# Sheet3.net
KiCad netlist of a schematic drawn in Altium Designer
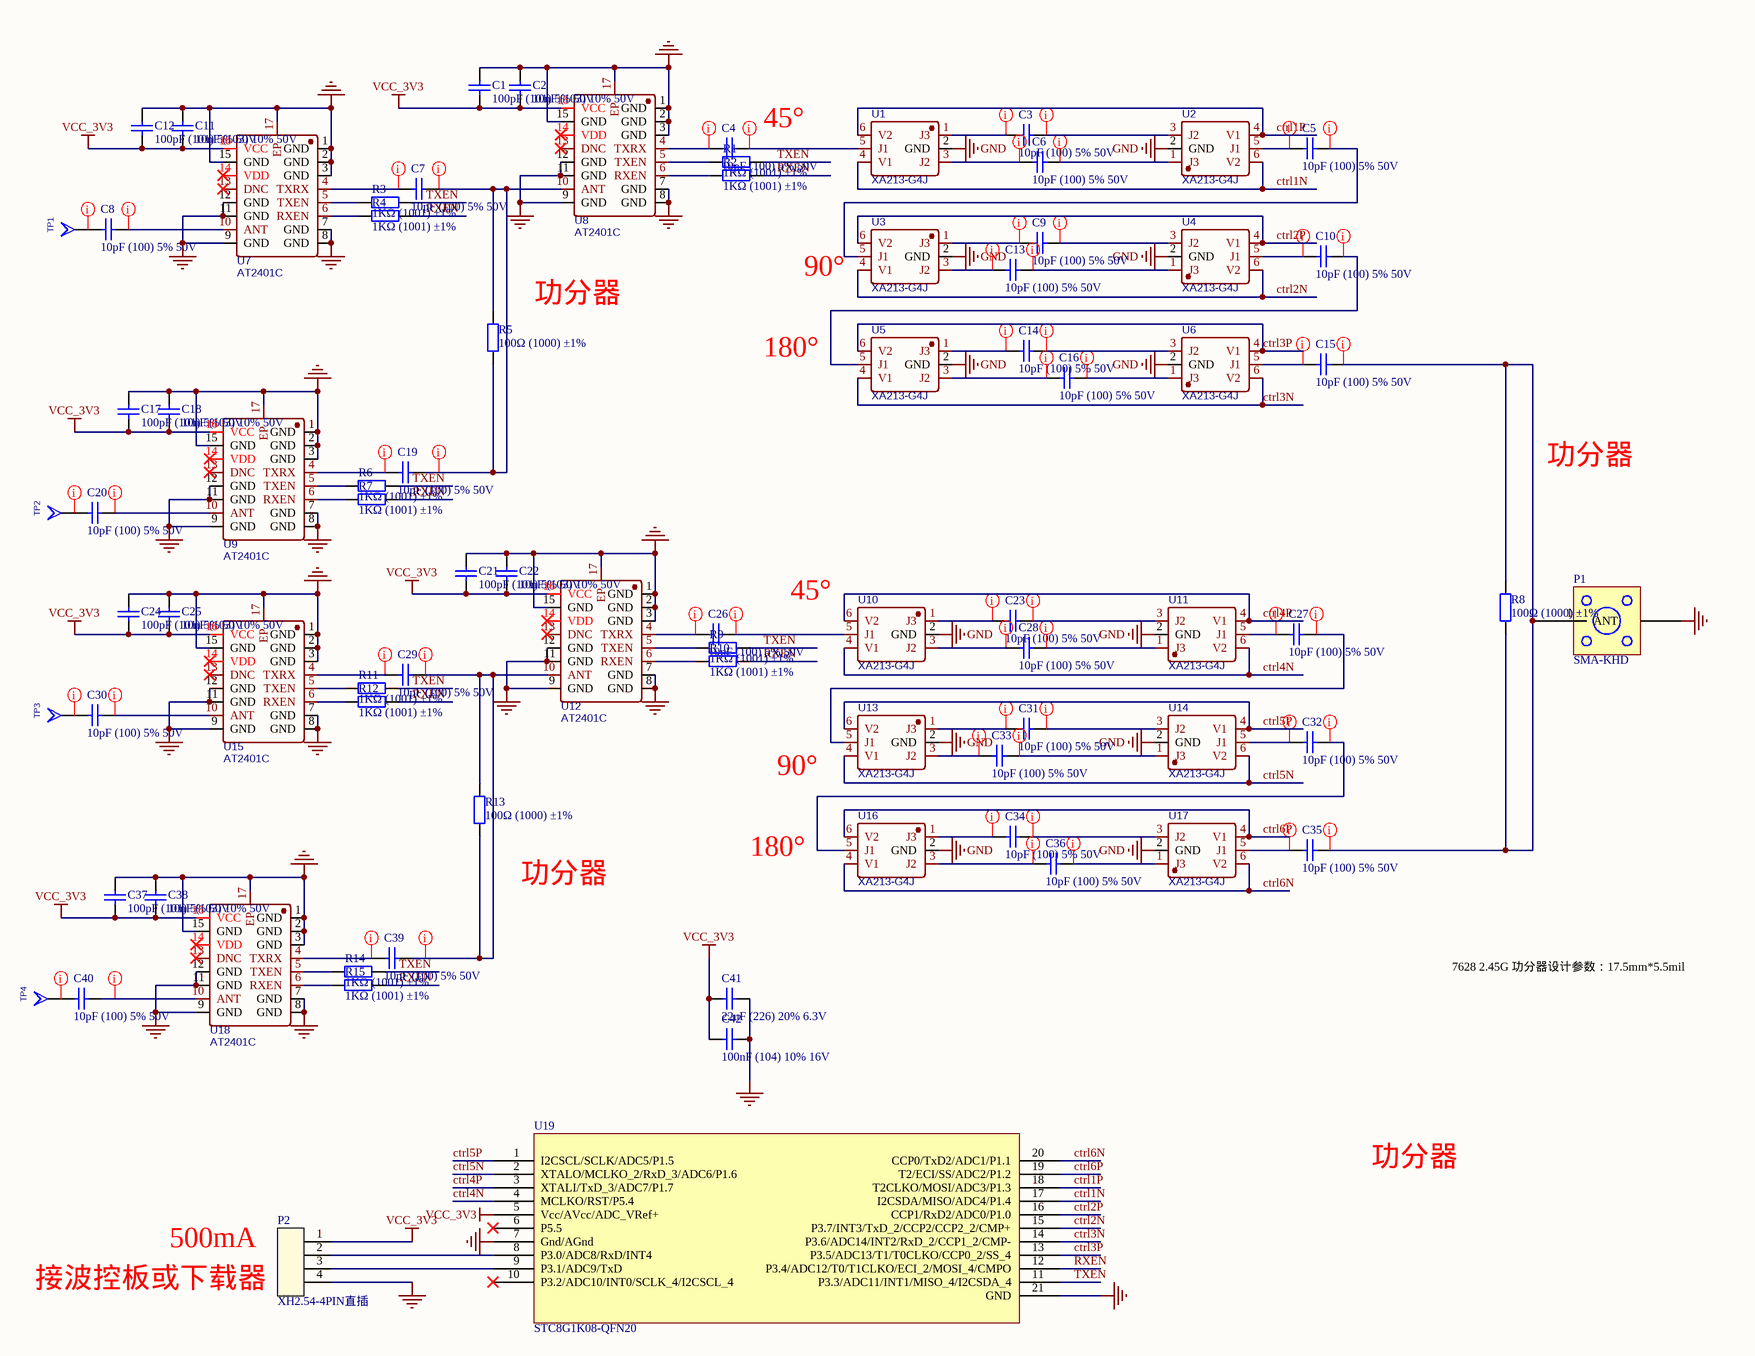
[diagram p0: Sheet3.SchDoc]

(export (version "E")
  (design (tool "Eeschema 10.0.6"))
  (components
    (comp (ref "C1")
      (value "100pF (101) 5% 50V")
      (footprint "0402_C")
      (description "贴片电容")
      (libsource (lib "ATE公司集成库") (part "0402 100pF (101) 5% 50V"))
    )
    (comp (ref "C2")
      (value "10nF (103) 10% 50V")
      (footprint "0402_C")
      (description "贴片电容")
      (libsource (lib "ATE公司集成库") (part "0402 10nF (103) 10% 50V"))
    )
    (comp (ref "C3")
      (value "10pF (100) 5% 50V")
      (footprint "0402_C")
      (description "贴片电容")
      (libsource (lib "ATE公司集成库") (part "0402 10pF (100) 5% 50V"))
    )
    (comp (ref "C4")
      (value "10pF (100) 5% 50V")
      (footprint "0402_C")
      (description "贴片电容")
      (libsource (lib "ATE公司集成库") (part "0402 10pF (100) 5% 50V"))
    )
    (comp (ref "C5")
      (value "10pF (100) 5% 50V")
      (footprint "0402_C")
      (description "贴片电容")
      (libsource (lib "ATE公司集成库") (part "0402 10pF (100) 5% 50V"))
    )
    (comp (ref "C6")
      (value "10pF (100) 5% 50V")
      (footprint "0402_C")
      (description "贴片电容")
      (libsource (lib "ATE公司集成库") (part "0402 10pF (100) 5% 50V"))
    )
    (comp (ref "C7")
      (value "10pF (100) 5% 50V")
      (footprint "0402_C")
      (description "贴片电容")
      (libsource (lib "ATE公司集成库") (part "0402 10pF (100) 5% 50V"))
    )
    (comp (ref "C8")
      (value "10pF (100) 5% 50V")
      (footprint "0402_C")
      (description "贴片电容")
      (libsource (lib "ATE公司集成库") (part "0402 10pF (100) 5% 50V"))
    )
    (comp (ref "C9")
      (value "10pF (100) 5% 50V")
      (footprint "0402_C")
      (description "贴片电容")
      (libsource (lib "ATE公司集成库") (part "0402 10pF (100) 5% 50V"))
    )
    (comp (ref "C10")
      (value "10pF (100) 5% 50V")
      (footprint "0402_C")
      (description "贴片电容")
      (libsource (lib "ATE公司集成库") (part "0402 10pF (100) 5% 50V"))
    )
    (comp (ref "C11")
      (value "10nF (103) 10% 50V")
      (footprint "0402_C")
      (description "贴片电容")
      (libsource (lib "ATE公司集成库") (part "0402 10nF (103) 10% 50V"))
    )
    (comp (ref "C12")
      (value "100pF (101) 5% 50V")
      (footprint "0402_C")
      (description "贴片电容")
      (libsource (lib "ATE公司集成库") (part "0402 100pF (101) 5% 50V"))
    )
    (comp (ref "C13")
      (value "10pF (100) 5% 50V")
      (footprint "0402_C")
      (description "贴片电容")
      (libsource (lib "ATE公司集成库") (part "0402 10pF (100) 5% 50V"))
    )
    (comp (ref "C14")
      (value "10pF (100) 5% 50V")
      (footprint "0402_C")
      (description "贴片电容")
      (libsource (lib "ATE公司集成库") (part "0402 10pF (100) 5% 50V"))
    )
    (comp (ref "C15")
      (value "10pF (100) 5% 50V")
      (footprint "0402_C")
      (description "贴片电容")
      (libsource (lib "ATE公司集成库") (part "0402 10pF (100) 5% 50V"))
    )
    (comp (ref "C16")
      (value "10pF (100) 5% 50V")
      (footprint "0402_C")
      (description "贴片电容")
      (libsource (lib "ATE公司集成库") (part "0402 10pF (100) 5% 50V"))
    )
    (comp (ref "C17")
      (value "100pF (101) 5% 50V")
      (footprint "0402_C")
      (description "贴片电容")
      (libsource (lib "ATE公司集成库") (part "0402 100pF (101) 5% 50V"))
    )
    (comp (ref "C18")
      (value "10nF (103) 10% 50V")
      (footprint "0402_C")
      (description "贴片电容")
      (libsource (lib "ATE公司集成库") (part "0402 10nF (103) 10% 50V"))
    )
    (comp (ref "C19")
      (value "10pF (100) 5% 50V")
      (footprint "0402_C")
      (description "贴片电容")
      (libsource (lib "ATE公司集成库") (part "0402 10pF (100) 5% 50V"))
    )
    (comp (ref "C20")
      (value "10pF (100) 5% 50V")
      (footprint "0402_C")
      (description "贴片电容")
      (libsource (lib "ATE公司集成库") (part "0402 10pF (100) 5% 50V"))
    )
    (comp (ref "C21")
      (value "100pF (101) 5% 50V")
      (footprint "0402_C")
      (description "贴片电容")
      (libsource (lib "ATE公司集成库") (part "0402 100pF (101) 5% 50V"))
    )
    (comp (ref "C22")
      (value "10nF (103) 10% 50V")
      (footprint "0402_C")
      (description "贴片电容")
      (libsource (lib "ATE公司集成库") (part "0402 10nF (103) 10% 50V"))
    )
    (comp (ref "C23")
      (value "10pF (100) 5% 50V")
      (footprint "0402_C")
      (description "贴片电容")
      (libsource (lib "ATE公司集成库") (part "0402 10pF (100) 5% 50V"))
    )
    (comp (ref "C24")
      (value "100pF (101) 5% 50V")
      (footprint "0402_C")
      (description "贴片电容")
      (libsource (lib "ATE公司集成库") (part "0402 100pF (101) 5% 50V"))
    )
    (comp (ref "C25")
      (value "10nF (103) 10% 50V")
      (footprint "0402_C")
      (description "贴片电容")
      (libsource (lib "ATE公司集成库") (part "0402 10nF (103) 10% 50V"))
    )
    (comp (ref "C26")
      (value "10pF (100) 5% 50V")
      (footprint "0402_C")
      (description "贴片电容")
      (libsource (lib "ATE公司集成库") (part "0402 10pF (100) 5% 50V"))
    )
    (comp (ref "C27")
      (value "10pF (100) 5% 50V")
      (footprint "0402_C")
      (description "贴片电容")
      (libsource (lib "ATE公司集成库") (part "0402 10pF (100) 5% 50V"))
    )
    (comp (ref "C28")
      (value "10pF (100) 5% 50V")
      (footprint "0402_C")
      (description "贴片电容")
      (libsource (lib "ATE公司集成库") (part "0402 10pF (100) 5% 50V"))
    )
    (comp (ref "C29")
      (value "10pF (100) 5% 50V")
      (footprint "0402_C")
      (description "贴片电容")
      (libsource (lib "ATE公司集成库") (part "0402 10pF (100) 5% 50V"))
    )
    (comp (ref "C30")
      (value "10pF (100) 5% 50V")
      (footprint "0402_C")
      (description "贴片电容")
      (libsource (lib "ATE公司集成库") (part "0402 10pF (100) 5% 50V"))
    )
    (comp (ref "C31")
      (value "10pF (100) 5% 50V")
      (footprint "0402_C")
      (description "贴片电容")
      (libsource (lib "ATE公司集成库") (part "0402 10pF (100) 5% 50V"))
    )
    (comp (ref "C32")
      (value "10pF (100) 5% 50V")
      (footprint "0402_C")
      (description "贴片电容")
      (libsource (lib "ATE公司集成库") (part "0402 10pF (100) 5% 50V"))
    )
    (comp (ref "C33")
      (value "10pF (100) 5% 50V")
      (footprint "0402_C")
      (description "贴片电容")
      (libsource (lib "ATE公司集成库") (part "0402 10pF (100) 5% 50V"))
    )
    (comp (ref "C34")
      (value "10pF (100) 5% 50V")
      (footprint "0402_C")
      (description "贴片电容")
      (libsource (lib "ATE公司集成库") (part "0402 10pF (100) 5% 50V"))
    )
    (comp (ref "C35")
      (value "10pF (100) 5% 50V")
      (footprint "0402_C")
      (description "贴片电容")
      (libsource (lib "ATE公司集成库") (part "0402 10pF (100) 5% 50V"))
    )
    (comp (ref "C36")
      (value "10pF (100) 5% 50V")
      (footprint "0402_C")
      (description "贴片电容")
      (libsource (lib "ATE公司集成库") (part "0402 10pF (100) 5% 50V"))
    )
    (comp (ref "C37")
      (value "100pF (101) 5% 50V")
      (footprint "0402_C")
      (description "贴片电容")
      (libsource (lib "ATE公司集成库") (part "0402 100pF (101) 5% 50V"))
    )
    (comp (ref "C38")
      (value "10nF (103) 10% 50V")
      (footprint "0402_C")
      (description "贴片电容")
      (libsource (lib "ATE公司集成库") (part "0402 10nF (103) 10% 50V"))
    )
    (comp (ref "C39")
      (value "10pF (100) 5% 50V")
      (footprint "0402_C")
      (description "贴片电容")
      (libsource (lib "ATE公司集成库") (part "0402 10pF (100) 5% 50V"))
    )
    (comp (ref "C40")
      (value "10pF (100) 5% 50V")
      (footprint "0402_C")
      (description "贴片电容")
      (libsource (lib "ATE公司集成库") (part "0402 10pF (100) 5% 50V"))
    )
    (comp (ref "C41")
      (value "22uF (226) 20% 6.3V")
      (footprint "0603_C")
      (description "贴片电容")
      (libsource (lib "ATE公司集成库") (part "0603 22uF (226) 20% 6.3V"))
    )
    (comp (ref "C42")
      (value "100nF (104) 10% 16V")
      (footprint "0402_C")
      (description "贴片电容")
      (libsource (lib "ATE公司集成库") (part "0402 100nF (104) 10% 16V"))
    )
    (comp (ref "P1")
      (value "SMA-KHD")
      (footprint "SMA-KHD")
      (description "SMA正插射频连接器")
      (libsource (lib "ATE公司集成库") (part "SMA-KHD"))
    )
    (comp (ref "P2")
      (value "XH2.54-4PIN直插")
      (footprint "XH2.54-4PIN直插")
      (description "XH2.54-4PIN直插连接器")
      (libsource (lib "ATE公司集成库") (part "XH2.54-4PIN直插"))
    )
    (comp (ref "R1")
      (value "1KΩ (1001) ±1%")
      (footprint "0402_R")
      (description "贴片电阻")
      (libsource (lib "ATE公司集成库") (part "0402 1KΩ (1001) 1%"))
    )
    (comp (ref "R2")
      (value "1KΩ (1001) ±1%")
      (footprint "0402_R")
      (description "贴片电阻")
      (libsource (lib "ATE公司集成库") (part "0402 1KΩ (1001) 1%"))
    )
    (comp (ref "R3")
      (value "1KΩ (1001) ±1%")
      (footprint "0402_R")
      (description "贴片电阻")
      (libsource (lib "ATE公司集成库") (part "0402 1KΩ (1001) 1%"))
    )
    (comp (ref "R4")
      (value "1KΩ (1001) ±1%")
      (footprint "0402_R")
      (description "贴片电阻")
      (libsource (lib "ATE公司集成库") (part "0402 1KΩ (1001) 1%"))
    )
    (comp (ref "R5")
      (value "100Ω (1000) ±1%")
      (footprint "0402_R")
      (description "贴片电阻")
      (libsource (lib "ATE公司集成库") (part "0402 100Ω (1000) 1%"))
    )
    (comp (ref "R6")
      (value "1KΩ (1001) ±1%")
      (footprint "0402_R")
      (description "贴片电阻")
      (libsource (lib "ATE公司集成库") (part "0402 1KΩ (1001) 1%"))
    )
    (comp (ref "R7")
      (value "1KΩ (1001) ±1%")
      (footprint "0402_R")
      (description "贴片电阻")
      (libsource (lib "ATE公司集成库") (part "0402 1KΩ (1001) 1%"))
    )
    (comp (ref "R8")
      (value "100Ω (1000) ±1%")
      (footprint "0402_R")
      (description "贴片电阻")
      (libsource (lib "ATE公司集成库") (part "0402 100Ω (1000) 1%"))
    )
    (comp (ref "R9")
      (value "1KΩ (1001) ±1%")
      (footprint "0402_R")
      (description "贴片电阻")
      (libsource (lib "ATE公司集成库") (part "0402 1KΩ (1001) 1%"))
    )
    (comp (ref "R10")
      (value "1KΩ (1001) ±1%")
      (footprint "0402_R")
      (description "贴片电阻")
      (libsource (lib "ATE公司集成库") (part "0402 1KΩ (1001) 1%"))
    )
    (comp (ref "R11")
      (value "1KΩ (1001) ±1%")
      (footprint "0402_R")
      (description "贴片电阻")
      (libsource (lib "ATE公司集成库") (part "0402 1KΩ (1001) 1%"))
    )
    (comp (ref "R12")
      (value "1KΩ (1001) ±1%")
      (footprint "0402_R")
      (description "贴片电阻")
      (libsource (lib "ATE公司集成库") (part "0402 1KΩ (1001) 1%"))
    )
    (comp (ref "R13")
      (value "100Ω (1000) ±1%")
      (footprint "0402_R")
      (description "贴片电阻")
      (libsource (lib "ATE公司集成库") (part "0402 100Ω (1000) 1%"))
    )
    (comp (ref "R14")
      (value "1KΩ (1001) ±1%")
      (footprint "0402_R")
      (description "贴片电阻")
      (libsource (lib "ATE公司集成库") (part "0402 1KΩ (1001) 1%"))
    )
    (comp (ref "R15")
      (value "1KΩ (1001) ±1%")
      (footprint "0402_R")
      (description "贴片电阻")
      (libsource (lib "ATE公司集成库") (part "0402 1KΩ (1001) 1%"))
    )
    (comp (ref "TP1") (value "TP-1") (footprint "040_TESTPOINT") (libsource (lib "ATE公司集成库") (part "TP-1")))
    (comp (ref "TP2") (value "TP-1") (footprint "040_TESTPOINT") (libsource (lib "ATE公司集成库") (part "TP-1")))
    (comp (ref "TP3") (value "TP-1") (footprint "040_TESTPOINT") (libsource (lib "ATE公司集成库") (part "TP-1")))
    (comp (ref "TP4") (value "TP-1") (footprint "040_TESTPOINT") (libsource (lib "ATE公司集成库") (part "TP-1")))
    (comp (ref "U1")
      (value "XA213-G4J")
      (footprint "SOT-363_L2.0-W1.3-P0.65-LS2.1-BR")
      (fields (field (name "BOM_SUPPLIER PART") "C556294") (field (name "CONTRIBUTOR") "LCSC"))
      (libsource (lib "altium-import") (part "root_0_mirrored_XA213-G4J_"))
    )
    (comp (ref "U2")
      (value "XA213-G4J")
      (footprint "SOT-363_L2.0-W1.3-P0.65-LS2.1-BR")
      (fields (field (name "BOM_SUPPLIER PART") "C556294") (field (name "CONTRIBUTOR") "LCSC"))
      (libsource (lib "altium-import") (part "root_2_mirrored_XA213-G4J_"))
    )
    (comp (ref "U3")
      (value "XA213-G4J")
      (footprint "SOT-363_L2.0-W1.3-P0.65-LS2.1-BR")
      (fields (field (name "BOM_SUPPLIER PART") "C556294") (field (name "CONTRIBUTOR") "LCSC"))
      (libsource (lib "altium-import") (part "root_0_mirrored_XA213-G4J_"))
    )
    (comp (ref "U4")
      (value "XA213-G4J")
      (footprint "SOT-363_L2.0-W1.3-P0.65-LS2.1-BR")
      (fields (field (name "BOM_SUPPLIER PART") "C556294") (field (name "CONTRIBUTOR") "LCSC"))
      (libsource (lib "altium-import") (part "root_2_mirrored_XA213-G4J_"))
    )
    (comp (ref "U5")
      (value "XA213-G4J")
      (footprint "SOT-363_L2.0-W1.3-P0.65-LS2.1-BR")
      (fields (field (name "BOM_SUPPLIER PART") "C556294") (field (name "CONTRIBUTOR") "LCSC"))
      (libsource (lib "altium-import") (part "root_0_mirrored_XA213-G4J_"))
    )
    (comp (ref "U6")
      (value "XA213-G4J")
      (footprint "SOT-363_L2.0-W1.3-P0.65-LS2.1-BR")
      (fields (field (name "BOM_SUPPLIER PART") "C556294") (field (name "CONTRIBUTOR") "LCSC"))
      (libsource (lib "altium-import") (part "root_2_mirrored_XA213-G4J_"))
    )
    (comp (ref "U7")
      (value "AT2401C")
      (footprint "QFN-16_L3.0-W3.0-P0.50-BL-EP1.7")
      (fields (field (name "BOM_SUPPLIER PART") "C783588") (field (name "CONTRIBUTOR") "LCSC"))
      (libsource (lib "altium-import") (part "root_0_mirrored_AT2401C_"))
    )
    (comp (ref "U8")
      (value "AT2401C")
      (footprint "QFN-16_L3.0-W3.0-P0.50-BL-EP1.7")
      (fields (field (name "BOM_SUPPLIER PART") "C783588") (field (name "CONTRIBUTOR") "LCSC"))
      (libsource (lib "altium-import") (part "root_0_mirrored_AT2401C_"))
    )
    (comp (ref "U9")
      (value "AT2401C")
      (footprint "QFN-16_L3.0-W3.0-P0.50-BL-EP1.7")
      (fields (field (name "BOM_SUPPLIER PART") "C783588") (field (name "CONTRIBUTOR") "LCSC"))
      (libsource (lib "altium-import") (part "root_0_mirrored_AT2401C_"))
    )
    (comp (ref "U10")
      (value "XA213-G4J")
      (footprint "SOT-363_L2.0-W1.3-P0.65-LS2.1-BR")
      (fields (field (name "BOM_SUPPLIER PART") "C556294") (field (name "CONTRIBUTOR") "LCSC"))
      (libsource (lib "altium-import") (part "root_0_mirrored_XA213-G4J_"))
    )
    (comp (ref "U11")
      (value "XA213-G4J")
      (footprint "SOT-363_L2.0-W1.3-P0.65-LS2.1-BR")
      (fields (field (name "BOM_SUPPLIER PART") "C556294") (field (name "CONTRIBUTOR") "LCSC"))
      (libsource (lib "altium-import") (part "root_2_mirrored_XA213-G4J_"))
    )
    (comp (ref "U12")
      (value "AT2401C")
      (footprint "QFN-16_L3.0-W3.0-P0.50-BL-EP1.7")
      (fields (field (name "BOM_SUPPLIER PART") "C783588") (field (name "CONTRIBUTOR") "LCSC"))
      (libsource (lib "altium-import") (part "root_0_mirrored_AT2401C_"))
    )
    (comp (ref "U13")
      (value "XA213-G4J")
      (footprint "SOT-363_L2.0-W1.3-P0.65-LS2.1-BR")
      (fields (field (name "BOM_SUPPLIER PART") "C556294") (field (name "CONTRIBUTOR") "LCSC"))
      (libsource (lib "altium-import") (part "root_0_mirrored_XA213-G4J_"))
    )
    (comp (ref "U14")
      (value "XA213-G4J")
      (footprint "SOT-363_L2.0-W1.3-P0.65-LS2.1-BR")
      (fields (field (name "BOM_SUPPLIER PART") "C556294") (field (name "CONTRIBUTOR") "LCSC"))
      (libsource (lib "altium-import") (part "root_2_mirrored_XA213-G4J_"))
    )
    (comp (ref "U15")
      (value "AT2401C")
      (footprint "QFN-16_L3.0-W3.0-P0.50-BL-EP1.7")
      (fields (field (name "BOM_SUPPLIER PART") "C783588") (field (name "CONTRIBUTOR") "LCSC"))
      (libsource (lib "altium-import") (part "root_0_mirrored_AT2401C_"))
    )
    (comp (ref "U16")
      (value "XA213-G4J")
      (footprint "SOT-363_L2.0-W1.3-P0.65-LS2.1-BR")
      (fields (field (name "BOM_SUPPLIER PART") "C556294") (field (name "CONTRIBUTOR") "LCSC"))
      (libsource (lib "altium-import") (part "root_0_mirrored_XA213-G4J_"))
    )
    (comp (ref "U17")
      (value "XA213-G4J")
      (footprint "SOT-363_L2.0-W1.3-P0.65-LS2.1-BR")
      (fields (field (name "BOM_SUPPLIER PART") "C556294") (field (name "CONTRIBUTOR") "LCSC"))
      (libsource (lib "altium-import") (part "root_2_mirrored_XA213-G4J_"))
    )
    (comp (ref "U18")
      (value "AT2401C")
      (footprint "QFN-16_L3.0-W3.0-P0.50-BL-EP1.7")
      (fields (field (name "BOM_SUPPLIER PART") "C783588") (field (name "CONTRIBUTOR") "LCSC"))
      (libsource (lib "altium-import") (part "root_0_mirrored_AT2401C_"))
    )
    (comp (ref "U19")
      (value "STC8G1K08-QFN20")
      (footprint "QFN20(3x3)")
      (description "超小封装8位51单片机")
      (libsource (lib "ATE公司集成库") (part "STC8G1K08-QFN20"))
    )
  )
  (nets
    (net (code "1") (name "/RXEN") (class "Default")
      (node (ref "R10") (pin "2") (pinfunction "2_2") (pintype "passive"))
      (node (ref "R12") (pin "2") (pinfunction "2_2") (pintype "passive"))
      (node (ref "R15") (pin "2") (pinfunction "2_2") (pintype "passive"))
      (node (ref "R2") (pin "2") (pinfunction "2_2") (pintype "passive"))
      (node (ref "R4") (pin "2") (pinfunction "2_2") (pintype "passive"))
      (node (ref "R7") (pin "2") (pinfunction "2_2") (pintype "passive"))
      (node (ref "U19") (pin "12") (pinfunction "P3.4/ADC12/T0/T1CLKO/ECI_2/MOSI_4/CMPO_12") (pintype "passive"))
    )
    (net (code "2") (name "/TXEN") (class "Default")
      (node (ref "R1") (pin "2") (pinfunction "2_2") (pintype "passive"))
      (node (ref "R11") (pin "2") (pinfunction "2_2") (pintype "passive"))
      (node (ref "R14") (pin "2") (pinfunction "2_2") (pintype "passive"))
      (node (ref "R3") (pin "2") (pinfunction "2_2") (pintype "passive"))
      (node (ref "R6") (pin "2") (pinfunction "2_2") (pintype "passive"))
      (node (ref "R9") (pin "2") (pinfunction "2_2") (pintype "passive"))
      (node (ref "U19") (pin "11") (pinfunction "P3.3/ADC11/INT1/MISO_4/I2CSDA_4_11") (pintype "passive"))
    )
    (net (code "3") (name "/ctrl1N") (class "Default")
      (node (ref "U1") (pin "4") (pinfunction "V1_4") (pintype "passive"))
      (node (ref "U19") (pin "17") (pinfunction "I2CSDA/MISO/ADC4/P1.4_17") (pintype "passive"))
      (node (ref "U2") (pin "6") (pinfunction "V2_6") (pintype "passive"))
    )
    (net (code "4") (name "/ctrl1P") (class "Default")
      (node (ref "U1") (pin "6") (pinfunction "V2_6") (pintype "passive"))
      (node (ref "U19") (pin "18") (pinfunction "T2CLKO/MOSI/ADC3/P1.3_18") (pintype "passive"))
      (node (ref "U2") (pin "4") (pinfunction "V1_4") (pintype "passive"))
    )
    (net (code "5") (name "/ctrl2N") (class "Default")
      (node (ref "U19") (pin "15") (pinfunction "P3.7/INT3/TxD_2/CCP2/CCP2_2/CMP+_15") (pintype "passive"))
      (node (ref "U3") (pin "4") (pinfunction "V1_4") (pintype "passive"))
      (node (ref "U4") (pin "6") (pinfunction "V2_6") (pintype "passive"))
    )
    (net (code "6") (name "/ctrl2P") (class "Default")
      (node (ref "U19") (pin "16") (pinfunction "CCP1/RxD2/ADC0/P1.0_16") (pintype "passive"))
      (node (ref "U3") (pin "6") (pinfunction "V2_6") (pintype "passive"))
      (node (ref "U4") (pin "4") (pinfunction "V1_4") (pintype "passive"))
    )
    (net (code "7") (name "/ctrl3N") (class "Default")
      (node (ref "U19") (pin "14") (pinfunction "P3.6/ADC14/INT2/RxD_2/CCP1_2/CMP-_14") (pintype "passive"))
      (node (ref "U5") (pin "4") (pinfunction "V1_4") (pintype "passive"))
      (node (ref "U6") (pin "6") (pinfunction "V2_6") (pintype "passive"))
    )
    (net (code "8") (name "/ctrl3P") (class "Default")
      (node (ref "U19") (pin "13") (pinfunction "P3.5/ADC13/T1/T0CLKO/CCP0_2/SS_4_13") (pintype "passive"))
      (node (ref "U5") (pin "6") (pinfunction "V2_6") (pintype "passive"))
      (node (ref "U6") (pin "4") (pinfunction "V1_4") (pintype "passive"))
    )
    (net (code "9") (name "/ctrl4N") (class "Default")
      (node (ref "U10") (pin "4") (pinfunction "V1_4") (pintype "passive"))
      (node (ref "U11") (pin "6") (pinfunction "V2_6") (pintype "passive"))
      (node (ref "U19") (pin "4") (pinfunction "MCLKO/RST/P5.4_4") (pintype "passive"))
    )
    (net (code "10") (name "/ctrl4P") (class "Default")
      (node (ref "U10") (pin "6") (pinfunction "V2_6") (pintype "passive"))
      (node (ref "U11") (pin "4") (pinfunction "V1_4") (pintype "passive"))
      (node (ref "U19") (pin "3") (pinfunction "XTALI/TxD_3/ADC7/P1.7_3") (pintype "passive"))
    )
    (net (code "11") (name "/ctrl5N") (class "Default")
      (node (ref "U13") (pin "4") (pinfunction "V1_4") (pintype "passive"))
      (node (ref "U14") (pin "6") (pinfunction "V2_6") (pintype "passive"))
      (node (ref "U19") (pin "2") (pinfunction "XTALO/MCLKO_2/RxD_3/ADC6/P1.6_2") (pintype "passive"))
    )
    (net (code "12") (name "/ctrl5P") (class "Default")
      (node (ref "U13") (pin "6") (pinfunction "V2_6") (pintype "passive"))
      (node (ref "U14") (pin "4") (pinfunction "V1_4") (pintype "passive"))
      (node (ref "U19") (pin "1") (pinfunction "I2CSCL/SCLK/ADC5/P1.5_1") (pintype "passive"))
    )
    (net (code "13") (name "/ctrl6N") (class "Default")
      (node (ref "U16") (pin "4") (pinfunction "V1_4") (pintype "passive"))
      (node (ref "U17") (pin "6") (pinfunction "V2_6") (pintype "passive"))
      (node (ref "U19") (pin "20") (pinfunction "CCP0/TxD2/ADC1/P1.1_20") (pintype "passive"))
    )
    (net (code "14") (name "/ctrl6P") (class "Default")
      (node (ref "U16") (pin "6") (pinfunction "V2_6") (pintype "passive"))
      (node (ref "U17") (pin "4") (pinfunction "V1_4") (pintype "passive"))
      (node (ref "U19") (pin "19") (pinfunction "T2/ECI/SS/ADC2/P1.2_19") (pintype "passive"))
    )
    (net (code "15") (name "GND") (class "Default")
      (node (ref "C1") (pin "2") (pinfunction "2_2") (pintype "passive"))
      (node (ref "C11") (pin "2") (pinfunction "2_2") (pintype "passive"))
      (node (ref "C12") (pin "2") (pinfunction "2_2") (pintype "passive"))
      (node (ref "C17") (pin "2") (pinfunction "2_2") (pintype "passive"))
      (node (ref "C18") (pin "2") (pinfunction "2_2") (pintype "passive"))
      (node (ref "C2") (pin "2") (pinfunction "2_2") (pintype "passive"))
      (node (ref "C21") (pin "2") (pinfunction "2_2") (pintype "passive"))
      (node (ref "C22") (pin "2") (pinfunction "2_2") (pintype "passive"))
      (node (ref "C24") (pin "2") (pinfunction "2_2") (pintype "passive"))
      (node (ref "C25") (pin "2") (pinfunction "2_2") (pintype "passive"))
      (node (ref "C37") (pin "2") (pinfunction "2_2") (pintype "passive"))
      (node (ref "C38") (pin "2") (pinfunction "2_2") (pintype "passive"))
      (node (ref "C41") (pin "2") (pinfunction "2_2") (pintype "passive"))
      (node (ref "C42") (pin "2") (pinfunction "2_2") (pintype "passive"))
      (node (ref "P1") (pin "0") (pinfunction "GND_0") (pintype "passive"))
      (node (ref "P2") (pin "4") (pinfunction "4_4") (pintype "passive"))
      (node (ref "U1") (pin "2") (pinfunction "GND_2") (pintype "passive"))
      (node (ref "U10") (pin "2") (pinfunction "GND_2") (pintype "passive"))
      (node (ref "U11") (pin "2") (pinfunction "GND_2") (pintype "passive"))
      (node (ref "U12") (pin "1") (pinfunction "GND_1") (pintype "passive"))
      (node (ref "U12") (pin "11") (pinfunction "GND_11") (pintype "passive"))
      (node (ref "U12") (pin "12") (pinfunction "GND_12") (pintype "passive"))
      (node (ref "U12") (pin "15") (pinfunction "GND_15") (pintype "passive"))
      (node (ref "U12") (pin "17") (pinfunction "EP_17") (pintype "passive"))
      (node (ref "U12") (pin "2") (pinfunction "GND_2") (pintype "passive"))
      (node (ref "U12") (pin "3") (pinfunction "GND_3") (pintype "passive"))
      (node (ref "U12") (pin "7") (pinfunction "GND_7") (pintype "passive"))
      (node (ref "U12") (pin "8") (pinfunction "GND_8") (pintype "passive"))
      (node (ref "U12") (pin "9") (pinfunction "GND_9") (pintype "passive"))
      (node (ref "U13") (pin "2") (pinfunction "GND_2") (pintype "passive"))
      (node (ref "U14") (pin "2") (pinfunction "GND_2") (pintype "passive"))
      (node (ref "U15") (pin "1") (pinfunction "GND_1") (pintype "passive"))
      (node (ref "U15") (pin "11") (pinfunction "GND_11") (pintype "passive"))
      (node (ref "U15") (pin "12") (pinfunction "GND_12") (pintype "passive"))
      (node (ref "U15") (pin "15") (pinfunction "GND_15") (pintype "passive"))
      (node (ref "U15") (pin "17") (pinfunction "EP_17") (pintype "passive"))
      (node (ref "U15") (pin "2") (pinfunction "GND_2") (pintype "passive"))
      (node (ref "U15") (pin "3") (pinfunction "GND_3") (pintype "passive"))
      (node (ref "U15") (pin "7") (pinfunction "GND_7") (pintype "passive"))
      (node (ref "U15") (pin "8") (pinfunction "GND_8") (pintype "passive"))
      (node (ref "U15") (pin "9") (pinfunction "GND_9") (pintype "passive"))
      (node (ref "U16") (pin "2") (pinfunction "GND_2") (pintype "passive"))
      (node (ref "U17") (pin "2") (pinfunction "GND_2") (pintype "passive"))
      (node (ref "U18") (pin "1") (pinfunction "GND_1") (pintype "passive"))
      (node (ref "U18") (pin "11") (pinfunction "GND_11") (pintype "passive"))
      (node (ref "U18") (pin "12") (pinfunction "GND_12") (pintype "passive"))
      (node (ref "U18") (pin "15") (pinfunction "GND_15") (pintype "passive"))
      (node (ref "U18") (pin "17") (pinfunction "EP_17") (pintype "passive"))
      (node (ref "U18") (pin "2") (pinfunction "GND_2") (pintype "passive"))
      (node (ref "U18") (pin "3") (pinfunction "GND_3") (pintype "passive"))
      (node (ref "U18") (pin "7") (pinfunction "GND_7") (pintype "passive"))
      (node (ref "U18") (pin "8") (pinfunction "GND_8") (pintype "passive"))
      (node (ref "U18") (pin "9") (pinfunction "GND_9") (pintype "passive"))
      (node (ref "U19") (pin "21") (pinfunction "GND_21") (pintype "passive"))
      (node (ref "U19") (pin "7") (pinfunction "Gnd/AGnd_7") (pintype "passive"))
      (node (ref "U2") (pin "2") (pinfunction "GND_2") (pintype "passive"))
      (node (ref "U3") (pin "2") (pinfunction "GND_2") (pintype "passive"))
      (node (ref "U4") (pin "2") (pinfunction "GND_2") (pintype "passive"))
      (node (ref "U5") (pin "2") (pinfunction "GND_2") (pintype "passive"))
      (node (ref "U6") (pin "2") (pinfunction "GND_2") (pintype "passive"))
      (node (ref "U7") (pin "1") (pinfunction "GND_1") (pintype "passive"))
      (node (ref "U7") (pin "11") (pinfunction "GND_11") (pintype "passive"))
      (node (ref "U7") (pin "12") (pinfunction "GND_12") (pintype "passive"))
      (node (ref "U7") (pin "15") (pinfunction "GND_15") (pintype "passive"))
      (node (ref "U7") (pin "17") (pinfunction "EP_17") (pintype "passive"))
      (node (ref "U7") (pin "2") (pinfunction "GND_2") (pintype "passive"))
      (node (ref "U7") (pin "3") (pinfunction "GND_3") (pintype "passive"))
      (node (ref "U7") (pin "7") (pinfunction "GND_7") (pintype "passive"))
      (node (ref "U7") (pin "8") (pinfunction "GND_8") (pintype "passive"))
      (node (ref "U7") (pin "9") (pinfunction "GND_9") (pintype "passive"))
      (node (ref "U8") (pin "1") (pinfunction "GND_1") (pintype "passive"))
      (node (ref "U8") (pin "11") (pinfunction "GND_11") (pintype "passive"))
      (node (ref "U8") (pin "12") (pinfunction "GND_12") (pintype "passive"))
      (node (ref "U8") (pin "15") (pinfunction "GND_15") (pintype "passive"))
      (node (ref "U8") (pin "17") (pinfunction "EP_17") (pintype "passive"))
      (node (ref "U8") (pin "2") (pinfunction "GND_2") (pintype "passive"))
      (node (ref "U8") (pin "3") (pinfunction "GND_3") (pintype "passive"))
      (node (ref "U8") (pin "7") (pinfunction "GND_7") (pintype "passive"))
      (node (ref "U8") (pin "8") (pinfunction "GND_8") (pintype "passive"))
      (node (ref "U8") (pin "9") (pinfunction "GND_9") (pintype "passive"))
      (node (ref "U9") (pin "1") (pinfunction "GND_1") (pintype "passive"))
      (node (ref "U9") (pin "11") (pinfunction "GND_11") (pintype "passive"))
      (node (ref "U9") (pin "12") (pinfunction "GND_12") (pintype "passive"))
      (node (ref "U9") (pin "15") (pinfunction "GND_15") (pintype "passive"))
      (node (ref "U9") (pin "17") (pinfunction "EP_17") (pintype "passive"))
      (node (ref "U9") (pin "2") (pinfunction "GND_2") (pintype "passive"))
      (node (ref "U9") (pin "3") (pinfunction "GND_3") (pintype "passive"))
      (node (ref "U9") (pin "7") (pinfunction "GND_7") (pintype "passive"))
      (node (ref "U9") (pin "8") (pinfunction "GND_8") (pintype "passive"))
      (node (ref "U9") (pin "9") (pinfunction "GND_9") (pintype "passive"))
    )
    (net (code "16") (name "Net-(P1-ANT)") (class "Default")
      (node (ref "C15") (pin "2") (pinfunction "2_2") (pintype "passive"))
      (node (ref "C35") (pin "2") (pinfunction "2_2") (pintype "passive"))
      (node (ref "P1") (pin "1") (pinfunction "ANT_1") (pintype "passive"))
      (node (ref "R8") (pin "1") (pinfunction "1_1") (pintype "passive"))
      (node (ref "R8") (pin "2") (pinfunction "2_2") (pintype "passive"))
    )
    (net (code "17") (name "Net-(TP1-1)") (class "Default")
      (node (ref "C8") (pin "1") (pinfunction "1_1") (pintype "passive"))
      (node (ref "TP1") (pin "A") (pinfunction "1_A") (pintype "passive"))
    )
    (net (code "18") (name "Net-(TP2-1)") (class "Default")
      (node (ref "C20") (pin "1") (pinfunction "1_1") (pintype "passive"))
      (node (ref "TP2") (pin "A") (pinfunction "1_A") (pintype "passive"))
    )
    (net (code "19") (name "Net-(TP3-1)") (class "Default")
      (node (ref "C30") (pin "1") (pinfunction "1_1") (pintype "passive"))
      (node (ref "TP3") (pin "A") (pinfunction "1_A") (pintype "passive"))
    )
    (net (code "20") (name "Net-(TP4-1)") (class "Default")
      (node (ref "C40") (pin "1") (pinfunction "1_1") (pintype "passive"))
      (node (ref "TP4") (pin "A") (pinfunction "1_A") (pintype "passive"))
    )
    (net (code "21") (name "Net-(U1-J1)") (class "Default")
      (node (ref "C4") (pin "2") (pinfunction "2_2") (pintype "passive"))
      (node (ref "U1") (pin "5") (pinfunction "J1_5") (pintype "passive"))
    )
    (net (code "22") (name "Net-(U1-J2)") (class "Default")
      (node (ref "C6") (pin "1") (pinfunction "1_1") (pintype "passive"))
      (node (ref "U1") (pin "3") (pinfunction "J2_3") (pintype "passive"))
    )
    (net (code "23") (name "Net-(U1-J3)") (class "Default")
      (node (ref "C3") (pin "1") (pinfunction "1_1") (pintype "passive"))
      (node (ref "U1") (pin "1") (pinfunction "J3_1") (pintype "passive"))
    )
    (net (code "24") (name "Net-(U2-J1)") (class "Default")
      (node (ref "C5") (pin "1") (pinfunction "1_1") (pintype "passive"))
      (node (ref "U2") (pin "5") (pinfunction "J1_5") (pintype "passive"))
    )
    (net (code "25") (name "Net-(U2-J2)") (class "Default")
      (node (ref "C3") (pin "2") (pinfunction "2_2") (pintype "passive"))
      (node (ref "U2") (pin "3") (pinfunction "J2_3") (pintype "passive"))
    )
    (net (code "26") (name "Net-(U2-J3)") (class "Default")
      (node (ref "C6") (pin "2") (pinfunction "2_2") (pintype "passive"))
      (node (ref "U2") (pin "1") (pinfunction "J3_1") (pintype "passive"))
    )
    (net (code "27") (name "Net-(U3-J1)") (class "Default")
      (node (ref "C5") (pin "2") (pinfunction "2_2") (pintype "passive"))
      (node (ref "U3") (pin "5") (pinfunction "J1_5") (pintype "passive"))
    )
    (net (code "28") (name "Net-(U3-J2)") (class "Default")
      (node (ref "C13") (pin "1") (pinfunction "1_1") (pintype "passive"))
      (node (ref "U3") (pin "3") (pinfunction "J2_3") (pintype "passive"))
    )
    (net (code "29") (name "Net-(U3-J3)") (class "Default")
      (node (ref "C9") (pin "1") (pinfunction "1_1") (pintype "passive"))
      (node (ref "U3") (pin "1") (pinfunction "J3_1") (pintype "passive"))
    )
    (net (code "30") (name "Net-(U4-J1)") (class "Default")
      (node (ref "C10") (pin "1") (pinfunction "1_1") (pintype "passive"))
      (node (ref "U4") (pin "5") (pinfunction "J1_5") (pintype "passive"))
    )
    (net (code "31") (name "Net-(U4-J2)") (class "Default")
      (node (ref "C9") (pin "2") (pinfunction "2_2") (pintype "passive"))
      (node (ref "U4") (pin "3") (pinfunction "J2_3") (pintype "passive"))
    )
    (net (code "32") (name "Net-(U4-J3)") (class "Default")
      (node (ref "C13") (pin "2") (pinfunction "2_2") (pintype "passive"))
      (node (ref "U4") (pin "1") (pinfunction "J3_1") (pintype "passive"))
    )
    (net (code "33") (name "Net-(U5-J1)") (class "Default")
      (node (ref "C10") (pin "2") (pinfunction "2_2") (pintype "passive"))
      (node (ref "U5") (pin "5") (pinfunction "J1_5") (pintype "passive"))
    )
    (net (code "34") (name "Net-(U5-J2)") (class "Default")
      (node (ref "C16") (pin "1") (pinfunction "1_1") (pintype "passive"))
      (node (ref "U5") (pin "3") (pinfunction "J2_3") (pintype "passive"))
    )
    (net (code "35") (name "Net-(U5-J3)") (class "Default")
      (node (ref "C14") (pin "1") (pinfunction "1_1") (pintype "passive"))
      (node (ref "U5") (pin "1") (pinfunction "J3_1") (pintype "passive"))
    )
    (net (code "36") (name "Net-(U6-J1)") (class "Default")
      (node (ref "C15") (pin "1") (pinfunction "1_1") (pintype "passive"))
      (node (ref "U6") (pin "5") (pinfunction "J1_5") (pintype "passive"))
    )
    (net (code "37") (name "Net-(U6-J2)") (class "Default")
      (node (ref "C14") (pin "2") (pinfunction "2_2") (pintype "passive"))
      (node (ref "U6") (pin "3") (pinfunction "J2_3") (pintype "passive"))
    )
    (net (code "38") (name "Net-(U6-J3)") (class "Default")
      (node (ref "C16") (pin "2") (pinfunction "2_2") (pintype "passive"))
      (node (ref "U6") (pin "1") (pinfunction "J3_1") (pintype "passive"))
    )
    (net (code "39") (name "Net-(U7-ANT)") (class "Default")
      (node (ref "C8") (pin "2") (pinfunction "2_2") (pintype "passive"))
      (node (ref "U7") (pin "10") (pinfunction "ANT_10") (pintype "passive"))
    )
    (net (code "40") (name "Net-(U7-RXEN)") (class "Default")
      (node (ref "R4") (pin "1") (pinfunction "1_1") (pintype "passive"))
      (node (ref "U7") (pin "6") (pinfunction "RXEN_6") (pintype "passive"))
    )
    (net (code "41") (name "Net-(U7-TXEN)") (class "Default")
      (node (ref "R3") (pin "1") (pinfunction "1_1") (pintype "passive"))
      (node (ref "U7") (pin "5") (pinfunction "TXEN_5") (pintype "passive"))
    )
    (net (code "42") (name "Net-(U7-TXRX)") (class "Default")
      (node (ref "C7") (pin "1") (pinfunction "1_1") (pintype "passive"))
      (node (ref "U7") (pin "4") (pinfunction "TXRX_4") (pintype "passive"))
    )
    (net (code "43") (name "Net-(U8-ANT)") (class "Default")
      (node (ref "C19") (pin "2") (pinfunction "2_2") (pintype "passive"))
      (node (ref "C7") (pin "2") (pinfunction "2_2") (pintype "passive"))
      (node (ref "R5") (pin "1") (pinfunction "1_1") (pintype "passive"))
      (node (ref "R5") (pin "2") (pinfunction "2_2") (pintype "passive"))
      (node (ref "U8") (pin "10") (pinfunction "ANT_10") (pintype "passive"))
    )
    (net (code "44") (name "Net-(U8-RXEN)") (class "Default")
      (node (ref "R2") (pin "1") (pinfunction "1_1") (pintype "passive"))
      (node (ref "U8") (pin "6") (pinfunction "RXEN_6") (pintype "passive"))
    )
    (net (code "45") (name "Net-(U8-TXEN)") (class "Default")
      (node (ref "R1") (pin "1") (pinfunction "1_1") (pintype "passive"))
      (node (ref "U8") (pin "5") (pinfunction "TXEN_5") (pintype "passive"))
    )
    (net (code "46") (name "Net-(U8-TXRX)") (class "Default")
      (node (ref "C4") (pin "1") (pinfunction "1_1") (pintype "passive"))
      (node (ref "U8") (pin "4") (pinfunction "TXRX_4") (pintype "passive"))
    )
    (net (code "47") (name "Net-(U9-ANT)") (class "Default")
      (node (ref "C20") (pin "2") (pinfunction "2_2") (pintype "passive"))
      (node (ref "U9") (pin "10") (pinfunction "ANT_10") (pintype "passive"))
    )
    (net (code "48") (name "Net-(U9-RXEN)") (class "Default")
      (node (ref "R7") (pin "1") (pinfunction "1_1") (pintype "passive"))
      (node (ref "U9") (pin "6") (pinfunction "RXEN_6") (pintype "passive"))
    )
    (net (code "49") (name "Net-(U9-TXEN)") (class "Default")
      (node (ref "R6") (pin "1") (pinfunction "1_1") (pintype "passive"))
      (node (ref "U9") (pin "5") (pinfunction "TXEN_5") (pintype "passive"))
    )
    (net (code "50") (name "Net-(U9-TXRX)") (class "Default")
      (node (ref "C19") (pin "1") (pinfunction "1_1") (pintype "passive"))
      (node (ref "U9") (pin "4") (pinfunction "TXRX_4") (pintype "passive"))
    )
    (net (code "51") (name "Net-(U10-J1)") (class "Default")
      (node (ref "C26") (pin "2") (pinfunction "2_2") (pintype "passive"))
      (node (ref "U10") (pin "5") (pinfunction "J1_5") (pintype "passive"))
    )
    (net (code "52") (name "Net-(U10-J2)") (class "Default")
      (node (ref "C28") (pin "1") (pinfunction "1_1") (pintype "passive"))
      (node (ref "U10") (pin "3") (pinfunction "J2_3") (pintype "passive"))
    )
    (net (code "53") (name "Net-(U10-J3)") (class "Default")
      (node (ref "C23") (pin "1") (pinfunction "1_1") (pintype "passive"))
      (node (ref "U10") (pin "1") (pinfunction "J3_1") (pintype "passive"))
    )
    (net (code "54") (name "Net-(U11-J1)") (class "Default")
      (node (ref "C27") (pin "1") (pinfunction "1_1") (pintype "passive"))
      (node (ref "U11") (pin "5") (pinfunction "J1_5") (pintype "passive"))
    )
    (net (code "55") (name "Net-(U11-J2)") (class "Default")
      (node (ref "C23") (pin "2") (pinfunction "2_2") (pintype "passive"))
      (node (ref "U11") (pin "3") (pinfunction "J2_3") (pintype "passive"))
    )
    (net (code "56") (name "Net-(U11-J3)") (class "Default")
      (node (ref "C28") (pin "2") (pinfunction "2_2") (pintype "passive"))
      (node (ref "U11") (pin "1") (pinfunction "J3_1") (pintype "passive"))
    )
    (net (code "57") (name "Net-(U12-ANT)") (class "Default")
      (node (ref "C29") (pin "2") (pinfunction "2_2") (pintype "passive"))
      (node (ref "C39") (pin "2") (pinfunction "2_2") (pintype "passive"))
      (node (ref "R13") (pin "1") (pinfunction "1_1") (pintype "passive"))
      (node (ref "R13") (pin "2") (pinfunction "2_2") (pintype "passive"))
      (node (ref "U12") (pin "10") (pinfunction "ANT_10") (pintype "passive"))
    )
    (net (code "58") (name "Net-(U12-RXEN)") (class "Default")
      (node (ref "R10") (pin "1") (pinfunction "1_1") (pintype "passive"))
      (node (ref "U12") (pin "6") (pinfunction "RXEN_6") (pintype "passive"))
    )
    (net (code "59") (name "Net-(U12-TXEN)") (class "Default")
      (node (ref "R9") (pin "1") (pinfunction "1_1") (pintype "passive"))
      (node (ref "U12") (pin "5") (pinfunction "TXEN_5") (pintype "passive"))
    )
    (net (code "60") (name "Net-(U12-TXRX)") (class "Default")
      (node (ref "C26") (pin "1") (pinfunction "1_1") (pintype "passive"))
      (node (ref "U12") (pin "4") (pinfunction "TXRX_4") (pintype "passive"))
    )
    (net (code "61") (name "Net-(U13-J1)") (class "Default")
      (node (ref "C27") (pin "2") (pinfunction "2_2") (pintype "passive"))
      (node (ref "U13") (pin "5") (pinfunction "J1_5") (pintype "passive"))
    )
    (net (code "62") (name "Net-(U13-J2)") (class "Default")
      (node (ref "C33") (pin "1") (pinfunction "1_1") (pintype "passive"))
      (node (ref "U13") (pin "3") (pinfunction "J2_3") (pintype "passive"))
    )
    (net (code "63") (name "Net-(U13-J3)") (class "Default")
      (node (ref "C31") (pin "1") (pinfunction "1_1") (pintype "passive"))
      (node (ref "U13") (pin "1") (pinfunction "J3_1") (pintype "passive"))
    )
    (net (code "64") (name "Net-(U14-J1)") (class "Default")
      (node (ref "C32") (pin "1") (pinfunction "1_1") (pintype "passive"))
      (node (ref "U14") (pin "5") (pinfunction "J1_5") (pintype "passive"))
    )
    (net (code "65") (name "Net-(U14-J2)") (class "Default")
      (node (ref "C31") (pin "2") (pinfunction "2_2") (pintype "passive"))
      (node (ref "U14") (pin "3") (pinfunction "J2_3") (pintype "passive"))
    )
    (net (code "66") (name "Net-(U14-J3)") (class "Default")
      (node (ref "C33") (pin "2") (pinfunction "2_2") (pintype "passive"))
      (node (ref "U14") (pin "1") (pinfunction "J3_1") (pintype "passive"))
    )
    (net (code "67") (name "Net-(U15-ANT)") (class "Default")
      (node (ref "C30") (pin "2") (pinfunction "2_2") (pintype "passive"))
      (node (ref "U15") (pin "10") (pinfunction "ANT_10") (pintype "passive"))
    )
    (net (code "68") (name "Net-(U15-RXEN)") (class "Default")
      (node (ref "R12") (pin "1") (pinfunction "1_1") (pintype "passive"))
      (node (ref "U15") (pin "6") (pinfunction "RXEN_6") (pintype "passive"))
    )
    (net (code "69") (name "Net-(U15-TXEN)") (class "Default")
      (node (ref "R11") (pin "1") (pinfunction "1_1") (pintype "passive"))
      (node (ref "U15") (pin "5") (pinfunction "TXEN_5") (pintype "passive"))
    )
    (net (code "70") (name "Net-(U15-TXRX)") (class "Default")
      (node (ref "C29") (pin "1") (pinfunction "1_1") (pintype "passive"))
      (node (ref "U15") (pin "4") (pinfunction "TXRX_4") (pintype "passive"))
    )
    (net (code "71") (name "Net-(U16-J1)") (class "Default")
      (node (ref "C32") (pin "2") (pinfunction "2_2") (pintype "passive"))
      (node (ref "U16") (pin "5") (pinfunction "J1_5") (pintype "passive"))
    )
    (net (code "72") (name "Net-(U16-J2)") (class "Default")
      (node (ref "C36") (pin "1") (pinfunction "1_1") (pintype "passive"))
      (node (ref "U16") (pin "3") (pinfunction "J2_3") (pintype "passive"))
    )
    (net (code "73") (name "Net-(U16-J3)") (class "Default")
      (node (ref "C34") (pin "1") (pinfunction "1_1") (pintype "passive"))
      (node (ref "U16") (pin "1") (pinfunction "J3_1") (pintype "passive"))
    )
    (net (code "74") (name "Net-(U17-J1)") (class "Default")
      (node (ref "C35") (pin "1") (pinfunction "1_1") (pintype "passive"))
      (node (ref "U17") (pin "5") (pinfunction "J1_5") (pintype "passive"))
    )
    (net (code "75") (name "Net-(U17-J2)") (class "Default")
      (node (ref "C34") (pin "2") (pinfunction "2_2") (pintype "passive"))
      (node (ref "U17") (pin "3") (pinfunction "J2_3") (pintype "passive"))
    )
    (net (code "76") (name "Net-(U17-J3)") (class "Default")
      (node (ref "C36") (pin "2") (pinfunction "2_2") (pintype "passive"))
      (node (ref "U17") (pin "1") (pinfunction "J3_1") (pintype "passive"))
    )
    (net (code "77") (name "Net-(U18-ANT)") (class "Default")
      (node (ref "C40") (pin "2") (pinfunction "2_2") (pintype "passive"))
      (node (ref "U18") (pin "10") (pinfunction "ANT_10") (pintype "passive"))
    )
    (net (code "78") (name "Net-(U18-RXEN)") (class "Default")
      (node (ref "R15") (pin "1") (pinfunction "1_1") (pintype "passive"))
      (node (ref "U18") (pin "6") (pinfunction "RXEN_6") (pintype "passive"))
    )
    (net (code "79") (name "Net-(U18-TXEN)") (class "Default")
      (node (ref "R14") (pin "1") (pinfunction "1_1") (pintype "passive"))
      (node (ref "U18") (pin "5") (pinfunction "TXEN_5") (pintype "passive"))
    )
    (net (code "80") (name "Net-(U18-TXRX)") (class "Default")
      (node (ref "C39") (pin "1") (pinfunction "1_1") (pintype "passive"))
      (node (ref "U18") (pin "4") (pinfunction "TXRX_4") (pintype "passive"))
    )
    (net (code "81") (name "Net-(U19-P3.0{slash}ADC8{slash}RxD{slash}INT4)") (class "Default")
      (node (ref "P2") (pin "2") (pintype "passive"))
      (node (ref "U19") (pin "8") (pinfunction "P3.0/ADC8/RxD/INT4_8") (pintype "passive"))
    )
    (net (code "82") (name "Net-(U19-P3.1{slash}ADC9{slash}TxD)") (class "Default")
      (node (ref "P2") (pin "3") (pinfunction "3_3") (pintype "passive"))
      (node (ref "U19") (pin "9") (pinfunction "P3.1/ADC9/TxD_9") (pintype "passive"))
    )
    (net (code "83") (name "VCC_3V3") (class "Default")
      (node (ref "C1") (pin "1") (pinfunction "1_1") (pintype "passive"))
      (node (ref "C11") (pin "1") (pinfunction "1_1") (pintype "passive"))
      (node (ref "C12") (pin "1") (pinfunction "1_1") (pintype "passive"))
      (node (ref "C17") (pin "1") (pinfunction "1_1") (pintype "passive"))
      (node (ref "C18") (pin "1") (pinfunction "1_1") (pintype "passive"))
      (node (ref "C2") (pin "1") (pinfunction "1_1") (pintype "passive"))
      (node (ref "C21") (pin "1") (pinfunction "1_1") (pintype "passive"))
      (node (ref "C22") (pin "1") (pinfunction "1_1") (pintype "passive"))
      (node (ref "C24") (pin "1") (pinfunction "1_1") (pintype "passive"))
      (node (ref "C25") (pin "1") (pinfunction "1_1") (pintype "passive"))
      (node (ref "C37") (pin "1") (pinfunction "1_1") (pintype "passive"))
      (node (ref "C38") (pin "1") (pinfunction "1_1") (pintype "passive"))
      (node (ref "C41") (pin "1") (pinfunction "1_1") (pintype "passive"))
      (node (ref "C42") (pin "1") (pinfunction "1_1") (pintype "passive"))
      (node (ref "P2") (pin "1") (pintype "passive"))
      (node (ref "U12") (pin "16") (pinfunction "VCC_16") (pintype "passive"))
      (node (ref "U15") (pin "16") (pinfunction "VCC_16") (pintype "passive"))
      (node (ref "U18") (pin "16") (pinfunction "VCC_16") (pintype "passive"))
      (node (ref "U19") (pin "5") (pinfunction "Vcc/AVcc/ADC_VRef+_5") (pintype "passive"))
      (node (ref "U7") (pin "16") (pinfunction "VCC_16") (pintype "passive"))
      (node (ref "U8") (pin "16") (pinfunction "VCC_16") (pintype "passive"))
      (node (ref "U9") (pin "16") (pinfunction "VCC_16") (pintype "passive"))
    )
    (net (code "84") (name "unconnected-(U7-DNC-Pad13)") (class "Default")
      (node (ref "U7") (pin "13") (pinfunction "DNC_13") (pintype "passive+no_connect"))
    )
    (net (code "85") (name "unconnected-(U7-VDD-Pad14)") (class "Default")
      (node (ref "U7") (pin "14") (pinfunction "VDD_14") (pintype "passive+no_connect"))
    )
    (net (code "86") (name "unconnected-(U8-DNC-Pad13)") (class "Default")
      (node (ref "U8") (pin "13") (pinfunction "DNC_13") (pintype "passive+no_connect"))
    )
    (net (code "87") (name "unconnected-(U8-VDD-Pad14)") (class "Default")
      (node (ref "U8") (pin "14") (pinfunction "VDD_14") (pintype "passive+no_connect"))
    )
    (net (code "88") (name "unconnected-(U9-DNC-Pad13)") (class "Default")
      (node (ref "U9") (pin "13") (pinfunction "DNC_13") (pintype "passive+no_connect"))
    )
    (net (code "89") (name "unconnected-(U9-VDD-Pad14)") (class "Default")
      (node (ref "U9") (pin "14") (pinfunction "VDD_14") (pintype "passive+no_connect"))
    )
    (net (code "90") (name "unconnected-(U12-DNC-Pad13)") (class "Default")
      (node (ref "U12") (pin "13") (pinfunction "DNC_13") (pintype "passive+no_connect"))
    )
    (net (code "91") (name "unconnected-(U12-VDD-Pad14)") (class "Default")
      (node (ref "U12") (pin "14") (pinfunction "VDD_14") (pintype "passive+no_connect"))
    )
    (net (code "92") (name "unconnected-(U15-DNC-Pad13)") (class "Default")
      (node (ref "U15") (pin "13") (pinfunction "DNC_13") (pintype "passive+no_connect"))
    )
    (net (code "93") (name "unconnected-(U15-VDD-Pad14)") (class "Default")
      (node (ref "U15") (pin "14") (pinfunction "VDD_14") (pintype "passive+no_connect"))
    )
    (net (code "94") (name "unconnected-(U18-DNC-Pad13)") (class "Default")
      (node (ref "U18") (pin "13") (pinfunction "DNC_13") (pintype "passive+no_connect"))
    )
    (net (code "95") (name "unconnected-(U18-VDD-Pad14)") (class "Default")
      (node (ref "U18") (pin "14") (pinfunction "VDD_14") (pintype "passive+no_connect"))
    )
    (net (code "96") (name "unconnected-(U19-P3.2{slash}ADC10{slash}INT0{slash}SCLK_4{slash}I2CSCL_4-Pad10)") (class "Default")
      (node (ref "U19") (pin "10") (pinfunction "P3.2/ADC10/INT0/SCLK_4/I2CSCL_4_10") (pintype "passive+no_connect"))
    )
    (net (code "97") (name "unconnected-(U19-P5.5-Pad6)") (class "Default")
      (node (ref "U19") (pin "6") (pinfunction "P5.5_6") (pintype "passive+no_connect"))
    )
  )
)
